# OutputChannel.net
KiCad netlist of a schematic drawn in Altium Designer
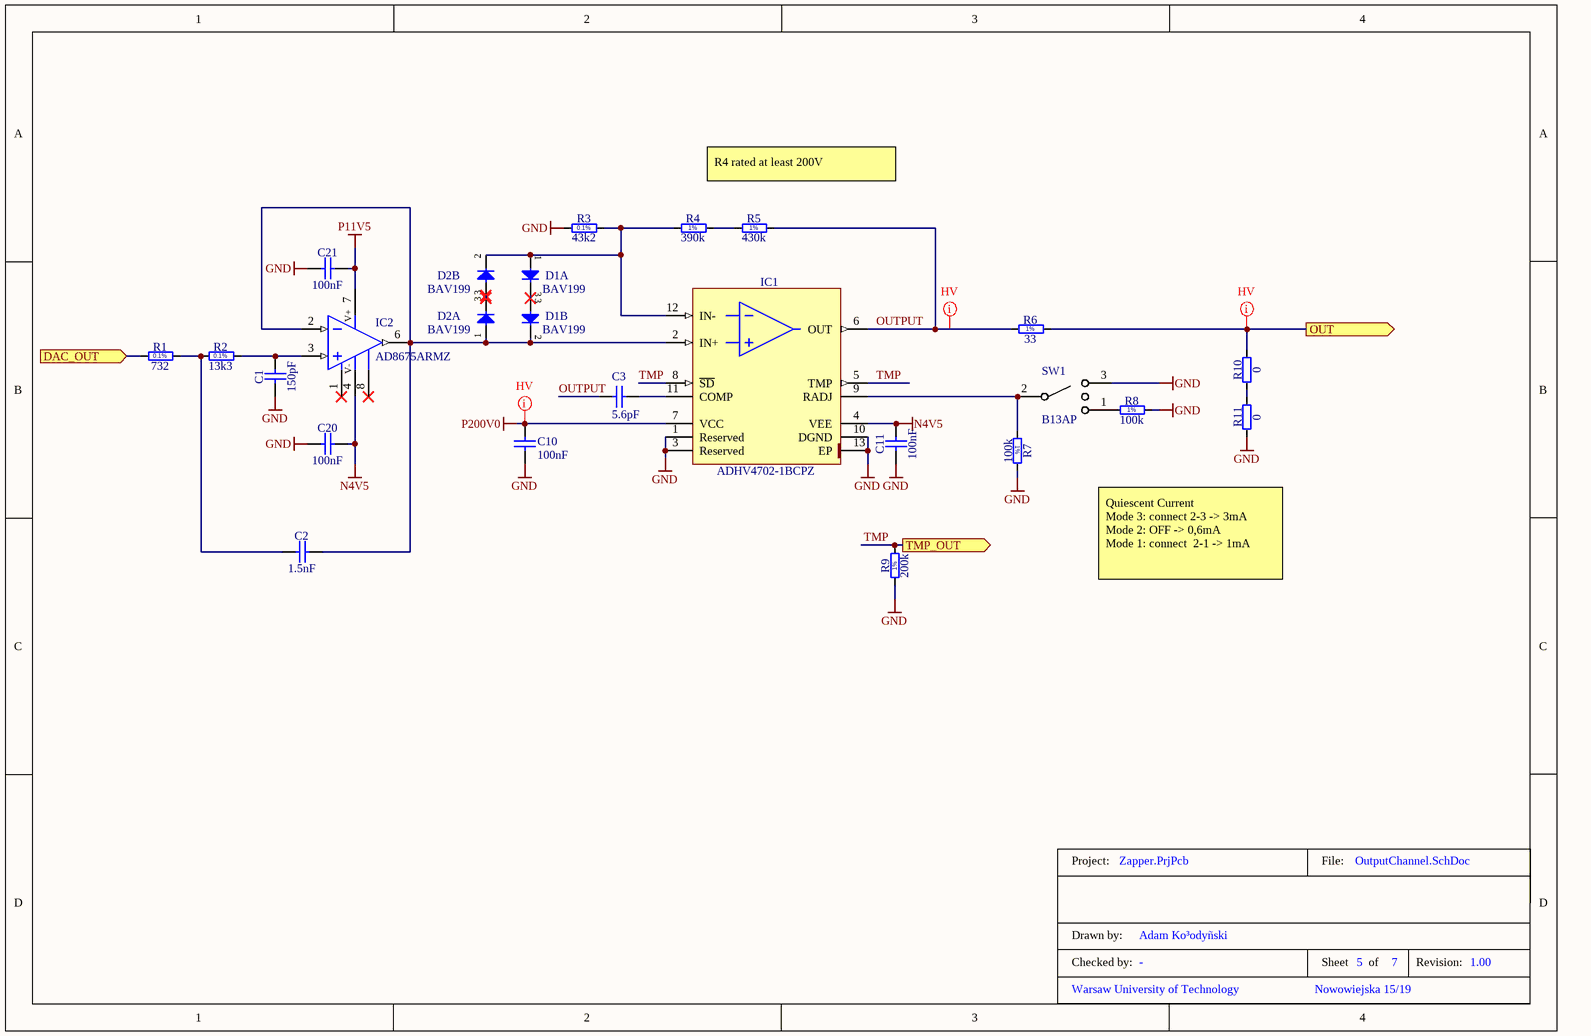
[diagram p0: OutputChannel.SchDoc]

(export (version "E")
  (design (tool "Eeschema 10.0.6"))
  (components
    (comp (ref "C1")
      (value "150pF")
      (footprint "CAPC1608X87N")
      (description "Non-polarised capacitor")
      (fields
        (field (name "PART NUMBER") "CC0603_150PF_50V_1%_NP0")
        (field (name "VOLTAGE") "50V")
        (field (name "AUTHOR") "CERN DEM MR")
      )
      (libsource (lib "Capacitors") (part "Capacitor - non polarized"))
    )
    (comp (ref "C2")
      (value "1.5nF")
      (footprint "CAPC1608X87N")
      (description "Non-polarised capacitor")
      (fields
        (field (name "PART NUMBER") "CC0603_1.5NF_50V_10%_X7R")
        (field (name "VOLTAGE") "50V")
        (field (name "AUTHOR") "CERN DEM JLC")
      )
      (libsource (lib "Capacitors") (part "Capacitor - non polarized"))
    )
    (comp (ref "C3")
      (value "5.6pF")
      (footprint "CAPC2012X95N - HV")
      (description "CAP CER 5.6PF 250V C0G/NP0 0805")
      (libsource (lib "CapacitorLibrary") (part "CBR08C569CAGAC"))
    )
    (comp (ref "C10")
      (value "100nF")
      (footprint "CAPC2012X125 - HV")
      (fields (field (name "TOLERANCE") "10%"))
      (libsource (lib "CapacitorLibrary") (part "C2012X7T2E104K125AA"))
    )
    (comp (ref "C11")
      (value "100nF")
      (footprint "CAPC1005X55N")
      (description "Non-polarised capacitor")
      (fields
        (field (name "PART NUMBER") "CC0402_100NF_16V_10%_X7R")
        (field (name "VOLTAGE") "16V")
        (field (name "AUTHOR") "CERN DEM JLC")
      )
      (libsource (lib "Capacitors") (part "Capacitor - non polarized"))
    )
    (comp (ref "C20")
      (value "100nF")
      (footprint "CAPC1005X55N")
      (description "Non-polarised capacitor")
      (fields
        (field (name "PART NUMBER") "CC0402_100NF_16V_10%_X7R")
        (field (name "VOLTAGE") "16V")
        (field (name "AUTHOR") "CERN DEM JLC")
      )
      (libsource (lib "Capacitors") (part "Capacitor - non polarized"))
    )
    (comp (ref "C21")
      (value "100nF")
      (footprint "CAPC1005X55N")
      (description "Non-polarised capacitor")
      (fields
        (field (name "PART NUMBER") "CC0402_100NF_16V_10%_X7R")
        (field (name "VOLTAGE") "16V")
        (field (name "AUTHOR") "CERN DEM JLC")
      )
      (libsource (lib "Capacitors") (part "Capacitor - non polarized"))
    )
    (comp (ref "D1")
      (value "BAV199")
      (footprint "SOT95P240X110-3N")
      (description "Serial Diode")
      (fields
        (field (name "VOLTAGE") "75V")
        (field (name "POWER") "250mW")
        (field (name "AUTHOR") "CERN DEM JMW")
      )
      (libsource (lib "ICs And Semiconductors") (part "Diode x2 A1C3_A3C2"))
    )
    (comp (ref "D2")
      (value "BAV199")
      (footprint "SOT95P240X110-3N")
      (description "Serial Diode")
      (fields
        (field (name "VOLTAGE") "75V")
        (field (name "POWER") "250mW")
        (field (name "AUTHOR") "CERN DEM JMW")
      )
      (libsource (lib "ICs And Semiconductors") (part "Diode x2 A1C3_A3C2"))
    )
    (comp (ref "IC1")
      (value "ADHV4702-1BCPZ")
      (footprint "QFN170P700X700X80-13N-S290")
      (description "24V to 220V Precision Operational Amplifier")
      (fields (field (name "MANUFACTURER") "ANALOG DEVICES") (field (name "AUTHOR") "CERN DEM BC"))
      (libsource (lib "ICs And Semiconductors") (part "ADHV4702-1"))
    )
    (comp (ref "IC2")
      (value "AD8675ARMZ")
      (footprint "SOP65P490X110-8N")
      (description "Operational Amplifier with Offset 1-8")
      (fields (field (name "MANUFACTURER") "ANALOG DEVICES") (field (name "AUTHOR") "CERN DEM JMW"))
      (libsource (lib "ICs And Semiconductors") (part "Operational Amplifier Type3"))
    )
    (comp (ref "R1")
      (value "732")
      (footprint "RESC1608X55N")
      (description "Resistor - 0.1%")
      (fields
        (field (name "PART NUMBER") "R0603_732R_0.1%_0.063W_10PPM")
        (field (name "POWER") "0.063W")
        (field (name "AUTHOR") "CERN DEM JLC")
      )
      (libsource (lib "Resistors") (part "Resistor - 0.1%"))
    )
    (comp (ref "R2")
      (value "13k3")
      (footprint "RESC1608X55N")
      (description "Resistor - 0.1%")
      (fields
        (field (name "PART NUMBER") "R0603_13K3_0.1%_0.063W_10PPM")
        (field (name "POWER") "0.063W")
        (field (name "AUTHOR") "CERN DEM JLC")
      )
      (libsource (lib "Resistors") (part "Resistor - 0.1%"))
    )
    (comp (ref "R3")
      (value "43k2")
      (footprint "RESC1608X55N")
      (description "Resistor - 0.1%")
      (fields
        (field (name "PART NUMBER") "R0603_43K2_0.1%_0.063W_10PPM")
        (field (name "POWER") "0.063W")
        (field (name "AUTHOR") "CERN DEM JLC")
      )
      (libsource (lib "Resistors") (part "Resistor - 0.1%"))
    )
    (comp (ref "R4")
      (value "390k")
      (footprint "RESC2012X60N")
      (description "Resistor - 1%")
      (fields
        (field (name "PART NUMBER") "R0805_390K_1%_0.125W_100PPM")
        (field (name "POWER") "0.125W")
        (field (name "AUTHOR") "CERN DEM JLC")
      )
      (libsource (lib "Resistors") (part "Resistor - 1%"))
    )
    (comp (ref "R5")
      (value "430k")
      (footprint "RESC2012X60N")
      (description "Resistor - 1%")
      (fields
        (field (name "PART NUMBER") "R0805_430K_1%_0.125W_100PPM")
        (field (name "POWER") "0.125W")
        (field (name "AUTHOR") "CERN DEM JLC")
      )
      (libsource (lib "Resistors") (part "Resistor - 1%"))
    )
    (comp (ref "R6")
      (value "33")
      (footprint "RESC1608X55N")
      (description "Resistor - 1%")
      (fields
        (field (name "PART NUMBER") "R0603_33R_1%_0.1W_100PPM")
        (field (name "POWER") "0.1W")
        (field (name "AUTHOR") "CERN DEM JLC")
      )
      (libsource (lib "Resistors") (part "Resistor - 1%"))
    )
    (comp (ref "R7")
      (value "100k")
      (footprint "RESC1608X55N")
      (description "Resistor - 1%")
      (fields
        (field (name "PART NUMBER") "R0603_100K_1%_0.1W_100PPM")
        (field (name "POWER") "0.1W")
        (field (name "AUTHOR") "CERN DEM JLC")
      )
      (libsource (lib "Resistors") (part "Resistor - 1%"))
    )
    (comp (ref "R8")
      (value "100k")
      (footprint "RESC1608X55N")
      (description "Resistor - 1%")
      (fields
        (field (name "PART NUMBER") "R0603_100K_1%_0.1W_100PPM")
        (field (name "POWER") "0.1W")
        (field (name "AUTHOR") "CERN DEM JLC")
      )
      (libsource (lib "Resistors") (part "Resistor - 1%"))
    )
    (comp (ref "R9")
      (value "200k")
      (footprint "RESC1608X55N")
      (description "Resistor - 1%")
      (fields
        (field (name "PART NUMBER") "R0603_200K_1%_0.1W_100PPM")
        (field (name "POWER") "0.1W")
        (field (name "AUTHOR") "CERN DEM JLC")
      )
      (libsource (lib "Resistors") (part "Resistor - 1%"))
    )
    (comp (ref "R10")
      (value "0")
      (footprint "RESC2012X60N")
      (description "Resistor")
      (fields
        (field (name "PART NUMBER") "R0805_0R_JUMPER")
        (field (name "MANUFACTURER") "GENERIC")
        (field (name "AUTHOR") "CERN DEM JLC")
      )
      (libsource (lib "Resistors") (part "Resistor"))
    )
    (comp (ref "R11")
      (value "0")
      (footprint "RESC2012X60N")
      (description "Resistor")
      (fields
        (field (name "PART NUMBER") "R0805_0R_JUMPER")
        (field (name "MANUFACTURER") "GENERIC")
        (field (name "AUTHOR") "CERN DEM JLC")
      )
      (libsource (lib "Resistors") (part "Resistor"))
    )
    (comp (ref "SW1")
      (value "B13AP")
      (footprint "B13AP")
      (description "Switch;  Sealed;  Anti-Static Toggle;  SPDT;  ON-OFF-ON;  Str PC;  No Cap;  0.4A;  28VAC/DC")
      (libsource (lib "InzLib") (part "B13AP"))
    )
    (comp (ref "TitleBlock5") (value "TitleBlock") (libsource (lib "InzLib") (part "TitleBlock")))
  )
  (nets
    (net (code "1") (name "/DAC_OUT") (class "Default")
      (node (ref "R1") (pin "1") (pinfunction "1_1") (pintype "passive"))
    )
    (net (code "2") (name "/OUT") (class "Default")
      (node (ref "R10") (pin "2") (pinfunction "2_2") (pintype "passive"))
      (node (ref "R6") (pin "2") (pinfunction "2_2") (pintype "passive"))
    )
    (net (code "3") (name "/OUTPUT") (class "Default")
      (node (ref "C3") (pin "2") (pinfunction "2_2") (pintype "passive"))
      (node (ref "IC1") (pin "6") (pinfunction "OUT_6") (pintype "output"))
      (node (ref "R5") (pin "2") (pinfunction "2_2") (pintype "passive"))
      (node (ref "R6") (pin "1") (pinfunction "1_1") (pintype "passive"))
    )
    (net (code "4") (name "/TMP") (class "Default")
      (node (ref "IC1") (pin "5") (pinfunction "TMP_5") (pintype "output"))
      (node (ref "IC1") (pin "8") (pinfunction "~{SD}_8") (pintype "input"))
      (node (ref "R9") (pin "2") (pinfunction "2_2") (pintype "passive"))
    )
    (net (code "5") (name "GND") (class "Default")
      (node (ref "C1") (pin "1") (pinfunction "1_1") (pintype "passive"))
      (node (ref "C10") (pin "1") (pinfunction "1_1") (pintype "passive"))
      (node (ref "C11") (pin "1") (pinfunction "1_1") (pintype "passive"))
      (node (ref "C20") (pin "1") (pinfunction "1_1") (pintype "passive"))
      (node (ref "C21") (pin "1") (pinfunction "1_1") (pintype "passive"))
      (node (ref "IC1") (pin "1") (pinfunction "Reserved_1") (pintype "passive"))
      (node (ref "IC1") (pin "10") (pinfunction "DGND_10") (pintype "power_in"))
      (node (ref "IC1") (pin "13") (pinfunction "EP_13") (pintype "passive"))
      (node (ref "IC1") (pin "3") (pinfunction "Reserved_3") (pintype "passive"))
      (node (ref "R11") (pin "1") (pinfunction "1_1") (pintype "passive"))
      (node (ref "R3") (pin "1") (pinfunction "1_1") (pintype "passive"))
      (node (ref "R7") (pin "2") (pinfunction "2_2") (pintype "passive"))
      (node (ref "R8") (pin "2") (pinfunction "2_2") (pintype "passive"))
      (node (ref "R9") (pin "1") (pinfunction "1_1") (pintype "passive"))
      (node (ref "SW1") (pin "3") (pinfunction "NC_3") (pintype "passive"))
    )
    (net (code "6") (name "N4V5") (class "Default")
      (node (ref "C11") (pin "2") (pinfunction "2_2") (pintype "passive"))
      (node (ref "C20") (pin "2") (pinfunction "2_2") (pintype "passive"))
      (node (ref "IC1") (pin "4") (pinfunction "VEE_4") (pintype "power_in"))
      (node (ref "IC2") (pin "4") (pinfunction "V-_4") (pintype "power_in"))
    )
    (net (code "7") (name "Net-(C2-Pad1)") (class "Default")
      (node (ref "C2") (pin "1") (pinfunction "1_1") (pintype "passive"))
      (node (ref "R1") (pin "2") (pinfunction "2_2") (pintype "passive"))
      (node (ref "R2") (pin "1") (pinfunction "1_1") (pintype "passive"))
    )
    (net (code "8") (name "Net-(D1A-A)") (class "Default")
      (node (ref "D1") (pin "1") (pinfunction "A_1") (pintype "passive"))
      (node (ref "D2") (pin "2") (pinfunction "C_2") (pintype "passive"))
      (node (ref "IC1") (pin "12") (pinfunction "IN-_12") (pintype "input"))
      (node (ref "R3") (pin "2") (pinfunction "2_2") (pintype "passive"))
      (node (ref "R4") (pin "1") (pinfunction "1_1") (pintype "passive"))
    )
    (net (code "9") (name "Net-(D1B-C)") (class "Default")
      (node (ref "C2") (pin "2") (pinfunction "2_2") (pintype "passive"))
      (node (ref "D1") (pin "2") (pinfunction "C_2") (pintype "passive"))
      (node (ref "D2") (pin "1") (pinfunction "A_1") (pintype "passive"))
      (node (ref "IC1") (pin "2") (pinfunction "IN+_2") (pintype "input"))
      (node (ref "IC2") (pin "2") (pinfunction "IN-_2") (pintype "input"))
      (node (ref "IC2") (pin "6") (pinfunction "OUT_6") (pintype "output"))
    )
    (net (code "10") (name "Net-(IC1-COMP)") (class "Default")
      (node (ref "C3") (pin "1") (pinfunction "1_1") (pintype "passive"))
      (node (ref "IC1") (pin "11") (pinfunction "COMP_11") (pintype "passive"))
    )
    (net (code "11") (name "Net-(IC1-RADJ)") (class "Default")
      (node (ref "IC1") (pin "9") (pinfunction "RADJ_9") (pintype "passive"))
      (node (ref "R7") (pin "1") (pinfunction "1_1") (pintype "passive"))
      (node (ref "SW1") (pin "2") (pinfunction "C_2") (pintype "passive"))
    )
    (net (code "12") (name "Net-(IC2-IN+)") (class "Default")
      (node (ref "C1") (pin "2") (pinfunction "2_2") (pintype "passive"))
      (node (ref "IC2") (pin "3") (pinfunction "IN+_3") (pintype "input"))
      (node (ref "R2") (pin "2") (pinfunction "2_2") (pintype "passive"))
    )
    (net (code "13") (name "Net-(R4-Pad2)") (class "Default")
      (node (ref "R4") (pin "2") (pinfunction "2_2") (pintype "passive"))
      (node (ref "R5") (pin "1") (pinfunction "1_1") (pintype "passive"))
    )
    (net (code "14") (name "Net-(R10-Pad1)") (class "Default")
      (node (ref "R10") (pin "1") (pinfunction "1_1") (pintype "passive"))
      (node (ref "R11") (pin "2") (pinfunction "2_2") (pintype "passive"))
    )
    (net (code "15") (name "Net-(SW1-NO)") (class "Default")
      (node (ref "R8") (pin "1") (pinfunction "1_1") (pintype "passive"))
      (node (ref "SW1") (pin "1") (pinfunction "NO_1") (pintype "passive"))
    )
    (net (code "16") (name "P11V5") (class "Default")
      (node (ref "C21") (pin "2") (pinfunction "2_2") (pintype "passive"))
      (node (ref "IC2") (pin "7") (pinfunction "V+_7") (pintype "power_in"))
    )
    (net (code "17") (name "P200V0") (class "Default")
      (node (ref "C10") (pin "2") (pinfunction "2_2") (pintype "passive"))
      (node (ref "IC1") (pin "7") (pinfunction "VCC_7") (pintype "power_in"))
    )
    (net (code "18") (name "unconnected-(D1A-COMAC-Pad3)") (class "Default")
      (node (ref "D1") (pin "3") (pinfunction "COMAC_3") (pintype "passive+no_connect"))
    )
    (net (code "19") (name "unconnected-(D2A-COMAC-Pad3)") (class "Default")
      (node (ref "D2") (pin "3") (pinfunction "COMAC_3") (pintype "passive+no_connect"))
    )
    (net (code "20") (name "unconnected-(IC2-OFFSET-Pad1)") (class "Default")
      (node (ref "IC2") (pin "1") (pinfunction "OFFSET_1") (pintype "passive+no_connect"))
    )
    (net (code "21") (name "unconnected-(IC2-OFFSET-Pad8)") (class "Default")
      (node (ref "IC2") (pin "8") (pinfunction "OFFSET_8") (pintype "passive+no_connect"))
    )
  )
)
